# MCU_board_in_foot_v1.net
KiCad netlist of a schematic drawn in EAGLE
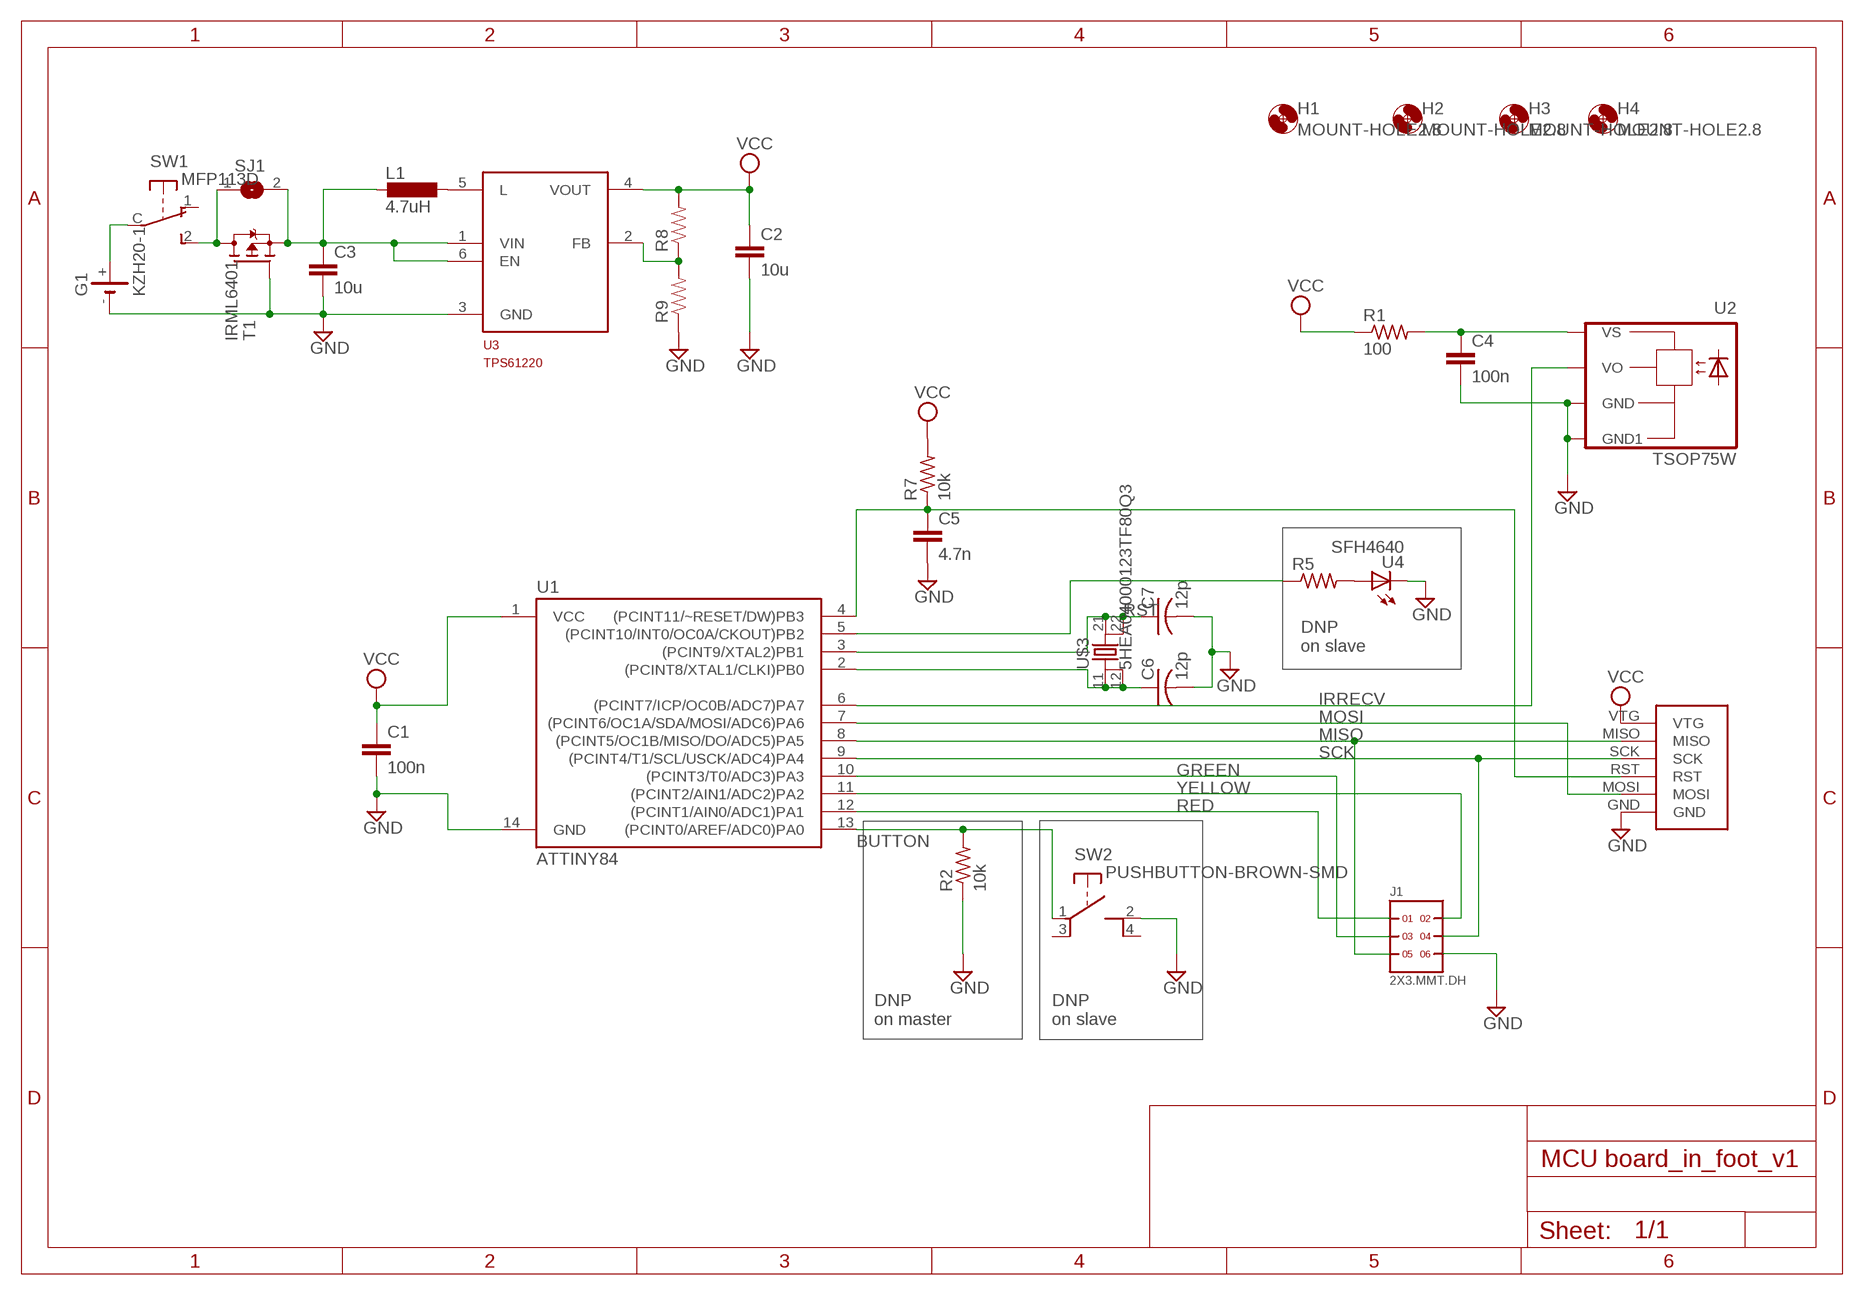
[diagram p0: schematic, sheet 1]

(export (version "E")
  (design (tool "Eeschema 10.0.6"))
  (components
    (comp (ref "C1")
      (value "100n")
      (footprint "eagle-import:0603-CAP")
      (libsource (lib "eagle-import") (part "CAP0603-CAP"))
    )
    (comp (ref "C2")
      (value "10u")
      (footprint "eagle-import:0603-CAP")
      (libsource (lib "eagle-import") (part "CAP0603-CAP"))
    )
    (comp (ref "C3")
      (value "10u")
      (footprint "eagle-import:0603-CAP")
      (libsource (lib "eagle-import") (part "MCU board_in_foot_99087_CAP0603-CAP"))
    )
    (comp (ref "C4")
      (value "100n")
      (footprint "eagle-import:0603-CAP")
      (libsource (lib "eagle-import") (part "CAP0603-CAP"))
    )
    (comp (ref "C5")
      (value "4.7n")
      (footprint "eagle-import:0603-CAP")
      (libsource (lib "eagle-import") (part "MCU board_in_foot_99087_CAP0603-CAP"))
    )
    (comp (ref "C6")
      (value "12p")
      (footprint "eagle-import:C0805")
      (libsource (lib "eagle-import") (part "C-USC0805"))
    )
    (comp (ref "C7")
      (value "12p")
      (footprint "eagle-import:C0805")
      (libsource (lib "eagle-import") (part "C-USC0805"))
    )
    (comp (ref "G1")
      (value "KZH20-1")
      (footprint "eagle-import:KZH20-1")
      (libsource (lib "eagle-import") (part "KZH20-1"))
    )
    (comp (ref "H1")
      (value "MOUNT-HOLE2.8")
      (footprint "eagle-import:2,8")
      (libsource (lib "eagle-import") (part "MCU board_in_foot_99087_MOUNT-HOLE2.8"))
    )
    (comp (ref "H2")
      (value "MOUNT-HOLE2.8")
      (footprint "eagle-import:2,8")
      (libsource (lib "eagle-import") (part "MOUNT-HOLE2.8"))
    )
    (comp (ref "H3")
      (value "MOUNT-HOLE2.8")
      (footprint "eagle-import:2,8")
      (libsource (lib "eagle-import") (part "MOUNT-HOLE2.8"))
    )
    (comp (ref "H4")
      (value "MOUNT-HOLE2.8")
      (footprint "eagle-import:2,8")
      (libsource (lib "eagle-import") (part "MCU board_in_foot_99087_MOUNT-HOLE2.8"))
    )
    (comp (ref "ISP")
      (value "ISP_POGOSURFACE")
      (footprint "eagle-import:ISP_SURFACE")
      (libsource (lib "eagle-import") (part "ISP_POGOSURFACE"))
    )
    (comp (ref "J1")
      (value "2X3.MMT.DH")
      (footprint "eagle-import:2X3_MMT.103.01.X.DH")
      (libsource (lib "eagle-import") (part "2X3.MMT.DH"))
    )
    (comp (ref "L1")
      (value "4.7uH")
      (footprint "eagle-import:EPL2010")
      (libsource (lib "eagle-import") (part "EPL2010"))
    )
    (comp (ref "R1")
      (value "100")
      (footprint "eagle-import:R0402")
      (libsource (lib "eagle-import") (part "R-US_R0402"))
    )
    (comp (ref "R2")
      (value "10k")
      (footprint "eagle-import:R0402")
      (libsource (lib "eagle-import") (part "R-US_R0402"))
    )
    (comp (ref "R5")
      (value "R-US_R0402")
      (footprint "eagle-import:R0402")
      (libsource (lib "eagle-import") (part "R-US_R0402"))
    )
    (comp (ref "R7")
      (value "10k")
      (footprint "eagle-import:R0402")
      (libsource (lib "eagle-import") (part "R-US_R0402"))
    )
    (comp (ref "R8")
      (value "RESISTOR0603-RES")
      (footprint "eagle-import:0603-RES")
      (libsource (lib "eagle-import") (part "RESISTOR0603-RES"))
    )
    (comp (ref "R9")
      (value "RESISTOR0603-RES")
      (footprint "eagle-import:0603-RES")
      (libsource (lib "eagle-import") (part "RESISTOR0603-RES"))
    )
    (comp (ref "SJ1") (value "SJ") (footprint "eagle-import:SJ") (libsource (lib "eagle-import") (part "SJ")))
    (comp (ref "SW1")
      (value "MFP113D")
      (footprint "eagle-import:MFP-SLIDER")
      (libsource (lib "eagle-import") (part "MFP113D"))
    )
    (comp (ref "SW2")
      (value "PUSHBUTTON-BROWN-SMD")
      (footprint "eagle-import:SMD-SW")
      (libsource (lib "eagle-import") (part "PUSHBUTTON-BROWN-SMD"))
    )
    (comp (ref "T1")
      (value "IRML6401")
      (footprint "eagle-import:SOT23")
      (libsource (lib "eagle-import") (part "IRML6401"))
    )
    (comp (ref "U$3")
      (value "5HEA04000123TF80Q3")
      (footprint "eagle-import:10X4.5MM")
      (libsource (lib "eagle-import") (part "5HEA04000123TF80Q3"))
    )
    (comp (ref "U1")
      (value "ATTINY84")
      (footprint "eagle-import:SO14")
      (libsource (lib "eagle-import") (part "ATTINY84"))
    )
    (comp (ref "U2")
      (value "TSOP75W")
      (footprint "eagle-import:TSOP75W-SIDELOOK")
      (libsource (lib "eagle-import") (part "TSOP75W"))
    )
    (comp (ref "U3")
      (value "TPS61220")
      (footprint "eagle-import:DCK-R_PDSO_G6")
      (libsource (lib "eagle-import") (part "TPS61220"))
    )
    (comp (ref "U4")
      (value "SFH4640")
      (footprint "eagle-import:MIDLED")
      (libsource (lib "eagle-import") (part "SFH4640"))
    )
  )
  (nets
    (net (code "1") (name "/BUTTON") (class "Default")
      (node (ref "R2") (pin "2") (pinfunction "2_2") (pintype "passive"))
      (node (ref "SW2") (pin "1") (pinfunction "P1_1") (pintype "passive"))
      (node (ref "U1") (pin "13") (pinfunction "(PCINT0/AREF/ADC0)PA0_13") (pintype "bidirectional"))
    )
    (net (code "2") (name "/GREEN") (class "Default")
      (node (ref "J1") (pin "3") (pinfunction "3_3") (pintype "bidirectional"))
      (node (ref "U1") (pin "10") (pinfunction "(PCINT3/T0/ADC3)PA3_10") (pintype "bidirectional"))
    )
    (net (code "3") (name "/IRRECV") (class "Default")
      (node (ref "U1") (pin "6") (pinfunction "(PCINT7/ICP/OC0B/ADC7)PA7_6") (pintype "bidirectional"))
      (node (ref "U2") (pin "3") (pinfunction "VO_3") (pintype "open_collector"))
    )
    (net (code "4") (name "/MISO") (class "Default")
      (node (ref "ISP") (pin "MISO") (pinfunction "MISO_MISO") (pintype "bidirectional"))
      (node (ref "J1") (pin "5") (pinfunction "5_5") (pintype "bidirectional"))
      (node (ref "U1") (pin "8") (pinfunction "(PCINT5/OC1B/MISO/DO/ADC5)PA5_8") (pintype "bidirectional"))
    )
    (net (code "5") (name "/MOSI") (class "Default")
      (node (ref "ISP") (pin "MOSI") (pinfunction "MOSI_MOSI") (pintype "bidirectional"))
      (node (ref "U1") (pin "7") (pinfunction "(PCINT6/OC1A/SDA/MOSI/ADC6)PA6_7") (pintype "bidirectional"))
    )
    (net (code "6") (name "/RED") (class "Default")
      (node (ref "J1") (pin "1") (pinfunction "1_1") (pintype "bidirectional"))
      (node (ref "U1") (pin "12") (pinfunction "(PCINT1/AIN0/ADC1)PA1_12") (pintype "bidirectional"))
    )
    (net (code "7") (name "/RST") (class "Default")
      (node (ref "C5") (pin "1") (pinfunction "1_1") (pintype "passive"))
      (node (ref "ISP") (pin "RST") (pinfunction "RST_RST") (pintype "bidirectional"))
      (node (ref "R7") (pin "1") (pinfunction "1_1") (pintype "passive"))
      (node (ref "U1") (pin "4") (pinfunction "(PCINT11/~{RESET/DW})PB3_4") (pintype "bidirectional"))
    )
    (net (code "8") (name "/SCK") (class "Default")
      (node (ref "ISP") (pin "SCK") (pinfunction "SCK_SCK") (pintype "bidirectional"))
      (node (ref "J1") (pin "4") (pinfunction "4_4") (pintype "bidirectional"))
      (node (ref "U1") (pin "9") (pinfunction "(PCINT4/T1/SCL/USCK/ADC4)PA4_9") (pintype "bidirectional"))
    )
    (net (code "9") (name "/YELLOW") (class "Default")
      (node (ref "J1") (pin "2") (pinfunction "2_2") (pintype "bidirectional"))
      (node (ref "U1") (pin "11") (pinfunction "(PCINT2/AIN1/ADC2)PA2_11") (pintype "bidirectional"))
    )
    (net (code "10") (name "GND") (class "Default")
      (node (ref "C1") (pin "2") (pinfunction "2_2") (pintype "passive"))
      (node (ref "C2") (pin "2") (pinfunction "2_2") (pintype "passive"))
      (node (ref "C3") (pin "2") (pinfunction "2_2") (pintype "passive"))
      (node (ref "C4") (pin "2") (pinfunction "2_2") (pintype "passive"))
      (node (ref "C5") (pin "2") (pinfunction "2_2") (pintype "passive"))
      (node (ref "C6") (pin "2") (pinfunction "2_2") (pintype "passive"))
      (node (ref "C7") (pin "2") (pinfunction "2_2") (pintype "passive"))
      (node (ref "G1") (pin "-") (pinfunction "-_-") (pintype "passive"))
      (node (ref "ISP") (pin "GND") (pinfunction "GND_GND") (pintype "bidirectional"))
      (node (ref "J1") (pin "6") (pinfunction "6_6") (pintype "bidirectional"))
      (node (ref "R2") (pin "1") (pinfunction "1_1") (pintype "passive"))
      (node (ref "R9") (pin "1") (pinfunction "1_1") (pintype "passive"))
      (node (ref "SW2") (pin "2") (pinfunction "S2_2") (pintype "passive"))
      (node (ref "T1") (pin "1") (pinfunction "G_1") (pintype "passive"))
      (node (ref "U1") (pin "14") (pinfunction "GND_14") (pintype "bidirectional"))
      (node (ref "U2") (pin "1") (pinfunction "GND_1") (pintype "power_in"))
      (node (ref "U2") (pin "4") (pinfunction "GND1_4") (pintype "power_in"))
      (node (ref "U3") (pin "3") (pinfunction "GND_3") (pintype "bidirectional"))
      (node (ref "U4") (pin "K") (pinfunction "C_K") (pintype "passive"))
    )
    (net (code "11") (name "Net-(L1-1)") (class "Default")
      (node (ref "C3") (pin "1") (pinfunction "1_1") (pintype "passive"))
      (node (ref "L1") (pin "P$1") (pinfunction "1_P$1") (pintype "passive"))
      (node (ref "SJ1") (pin "2") (pinfunction "2_2") (pintype "passive"))
      (node (ref "T1") (pin "2") (pinfunction "S_2") (pintype "passive"))
      (node (ref "U3") (pin "1") (pinfunction "VIN_1") (pintype "bidirectional"))
      (node (ref "U3") (pin "6") (pinfunction "EN_6") (pintype "bidirectional"))
    )
    (net (code "12") (name "Net-(L1-2)") (class "Default")
      (node (ref "L1") (pin "P$2") (pinfunction "2_P$2") (pintype "passive"))
      (node (ref "U3") (pin "5") (pinfunction "L_5") (pintype "bidirectional"))
    )
    (net (code "13") (name "Net-(R5-Pad2)") (class "Default")
      (node (ref "R5") (pin "2") (pinfunction "2_2") (pintype "passive"))
      (node (ref "U4") (pin "A") (pinfunction "A_A") (pintype "passive"))
    )
    (net (code "14") (name "Net-(SW1-P)") (class "Default")
      (node (ref "G1") (pin "+") (pinfunction "+_+") (pintype "passive"))
      (node (ref "SW1") (pin "C") (pinfunction "P_C") (pintype "passive"))
    )
    (net (code "15") (name "Net-(SW1-S)") (class "Default")
      (node (ref "SJ1") (pin "1") (pinfunction "1_1") (pintype "passive"))
      (node (ref "SW1") (pin "2") (pinfunction "S_2") (pintype "passive"))
      (node (ref "T1") (pin "3") (pinfunction "D_3") (pintype "passive"))
    )
    (net (code "16") (name "Net-(U1-(PCINT8{slash}XTAL1{slash}CLKI)PB0)") (class "Default")
      (node (ref "C6") (pin "1") (pinfunction "1_1") (pintype "passive"))
      (node (ref "U$3") (pin "11") (pinfunction "11_11") (pintype "passive"))
      (node (ref "U$3") (pin "12") (pinfunction "12_12") (pintype "passive"))
      (node (ref "U1") (pin "2") (pinfunction "(PCINT8/XTAL1/CLKI)PB0_2") (pintype "bidirectional"))
    )
    (net (code "17") (name "Net-(U1-(PCINT9{slash}XTAL2)PB1)") (class "Default")
      (node (ref "C7") (pin "1") (pinfunction "1_1") (pintype "passive"))
      (node (ref "U$3") (pin "21") (pinfunction "21_21") (pintype "passive"))
      (node (ref "U$3") (pin "22") (pinfunction "22_22") (pintype "passive"))
      (node (ref "U1") (pin "3") (pinfunction "(PCINT9/XTAL2)PB1_3") (pintype "bidirectional"))
    )
    (net (code "18") (name "Net-(U1-(PCINT10{slash}INT0{slash}OC0A{slash}CKOUT)PB2)") (class "Default")
      (node (ref "R5") (pin "1") (pinfunction "1_1") (pintype "passive"))
      (node (ref "U1") (pin "5") (pinfunction "(PCINT10/INT0/OC0A/CKOUT)PB2_5") (pintype "bidirectional"))
    )
    (net (code "19") (name "Net-(U2-VS)") (class "Default")
      (node (ref "C4") (pin "1") (pinfunction "1_1") (pintype "passive"))
      (node (ref "R1") (pin "2") (pinfunction "2_2") (pintype "passive"))
      (node (ref "U2") (pin "2") (pinfunction "VS_2") (pintype "power_in"))
    )
    (net (code "20") (name "Net-(U3-FB)") (class "Default")
      (node (ref "R8") (pin "1") (pinfunction "1_1") (pintype "passive"))
      (node (ref "R9") (pin "2") (pinfunction "2_2") (pintype "passive"))
      (node (ref "U3") (pin "2") (pinfunction "FB_2") (pintype "bidirectional"))
    )
    (net (code "21") (name "VCC") (class "Default")
      (node (ref "C1") (pin "1") (pinfunction "1_1") (pintype "passive"))
      (node (ref "C2") (pin "1") (pinfunction "1_1") (pintype "passive"))
      (node (ref "ISP") (pin "VTG") (pinfunction "VTG_VTG") (pintype "bidirectional"))
      (node (ref "R1") (pin "1") (pinfunction "1_1") (pintype "passive"))
      (node (ref "R7") (pin "2") (pinfunction "2_2") (pintype "passive"))
      (node (ref "R8") (pin "2") (pinfunction "2_2") (pintype "passive"))
      (node (ref "U1") (pin "1") (pinfunction "VCC_1") (pintype "bidirectional"))
      (node (ref "U3") (pin "4") (pinfunction "VOUT_4") (pintype "bidirectional"))
    )
    (net (code "22") (name "unconnected-(SW1-O-Pad1)") (class "Default")
      (node (ref "SW1") (pin "1") (pinfunction "O_1") (pintype "passive"))
    )
    (net (code "23") (name "unconnected-(SW2-P3-Pad3)") (class "Default")
      (node (ref "SW2") (pin "3") (pinfunction "P3_3") (pintype "passive"))
    )
    (net (code "24") (name "unconnected-(SW2-S4-Pad4)") (class "Default")
      (node (ref "SW2") (pin "4") (pinfunction "S4_4") (pintype "passive"))
    )
  )
)
